# Voltage_Regulator_5V.net
KiCad netlist of a schematic drawn in Altium Designer
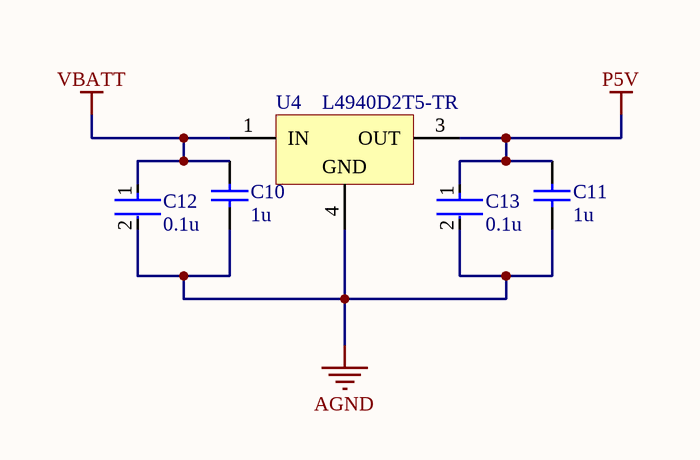
[diagram p0: Voltage_Regulator_5V.SchDoc]

(export (version "E")
  (design (tool "Eeschema 10.0.6"))
  (components
    (comp (ref "C10")
      (value "1u")
      (footprint "CAPC3216X110X50LL20T25")
      (description "Chip Capacitor, 1 uF, +/- 10%, 50 V, -55 to 125 degC, 1206 (3216 Metric), RoHS, Tape and Reel")
      (fields (field (name "MANUFACTURER") "Kemet") (field (name "TOLERANCE") "10%"))
      (libsource (lib "Altium Content Vault") (part "CAP-NP-2"))
    )
    (comp (ref "C11")
      (value "1u")
      (footprint "CAPC3216X110X50LL20T25")
      (description "Chip Capacitor, 1 uF, +/- 10%, 50 V, -55 to 125 degC, 1206 (3216 Metric), RoHS, Tape and Reel")
      (fields (field (name "MANUFACTURER") "Kemet") (field (name "TOLERANCE") "10%"))
      (libsource (lib "Altium Content Vault") (part "CAP-NP-2"))
    )
    (comp (ref "C12")
      (value "0.1u")
      (footprint "FP-C0402-BB-MFG")
      (description "CAP CER 0.1UF 10V X5R 0402")
      (fields (field (name "MANUFACTURER") "Kemet") (field (name "TOLERANCE") "0.1"))
      (libsource (lib "Altium Content Vault") (part "b4654b650e69147ec39a6b967a45e02"))
    )
    (comp (ref "C13")
      (value "0.1u")
      (footprint "FP-C0402-BB-MFG")
      (description "CAP CER 0.1UF 10V X5R 0402")
      (fields (field (name "MANUFACTURER") "Kemet") (field (name "TOLERANCE") "0.1"))
      (libsource (lib "Altium Content Vault") (part "b4654b650e69147ec39a6b967a45e02"))
    )
    (comp (ref "U4")
      (value "L4940D2T5-TR")
      (footprint "TO-263_M")
      (description "1.5A Very Low Drop Regulator, 3-Pin D2PAK, Tape and Reel")
      (libsource (lib "Altium Content Vault") (part "PM-REG-L4940-SOT3"))
    )
  )
  (nets
    (net (code "1") (name "AGND") (class "Default")
      (node (ref "C10") (pin "1") (pinfunction "1_1") (pintype "passive"))
      (node (ref "C11") (pin "1") (pinfunction "1_1") (pintype "passive"))
      (node (ref "C12") (pin "2") (pinfunction "2_2") (pintype "passive"))
      (node (ref "C13") (pin "2") (pinfunction "2_2") (pintype "passive"))
      (node (ref "U4") (pin "4") (pinfunction "GND_4") (pintype "power_in"))
    )
    (net (code "2") (name "P5V") (class "Default")
      (node (ref "C11") (pin "2") (pinfunction "2_2") (pintype "passive"))
      (node (ref "C13") (pin "1") (pinfunction "1_1") (pintype "passive"))
      (node (ref "U4") (pin "3") (pinfunction "OUT_3") (pintype "power_in"))
    )
    (net (code "3") (name "VBATT") (class "Default")
      (node (ref "C10") (pin "2") (pinfunction "2_2") (pintype "passive"))
      (node (ref "C12") (pin "1") (pinfunction "1_1") (pintype "passive"))
      (node (ref "U4") (pin "1") (pinfunction "IN_1") (pintype "power_in"))
    )
  )
)
